# 1A18J1_1A21J1_A.net
KiCad netlist of a schematic drawn in Altium Designer
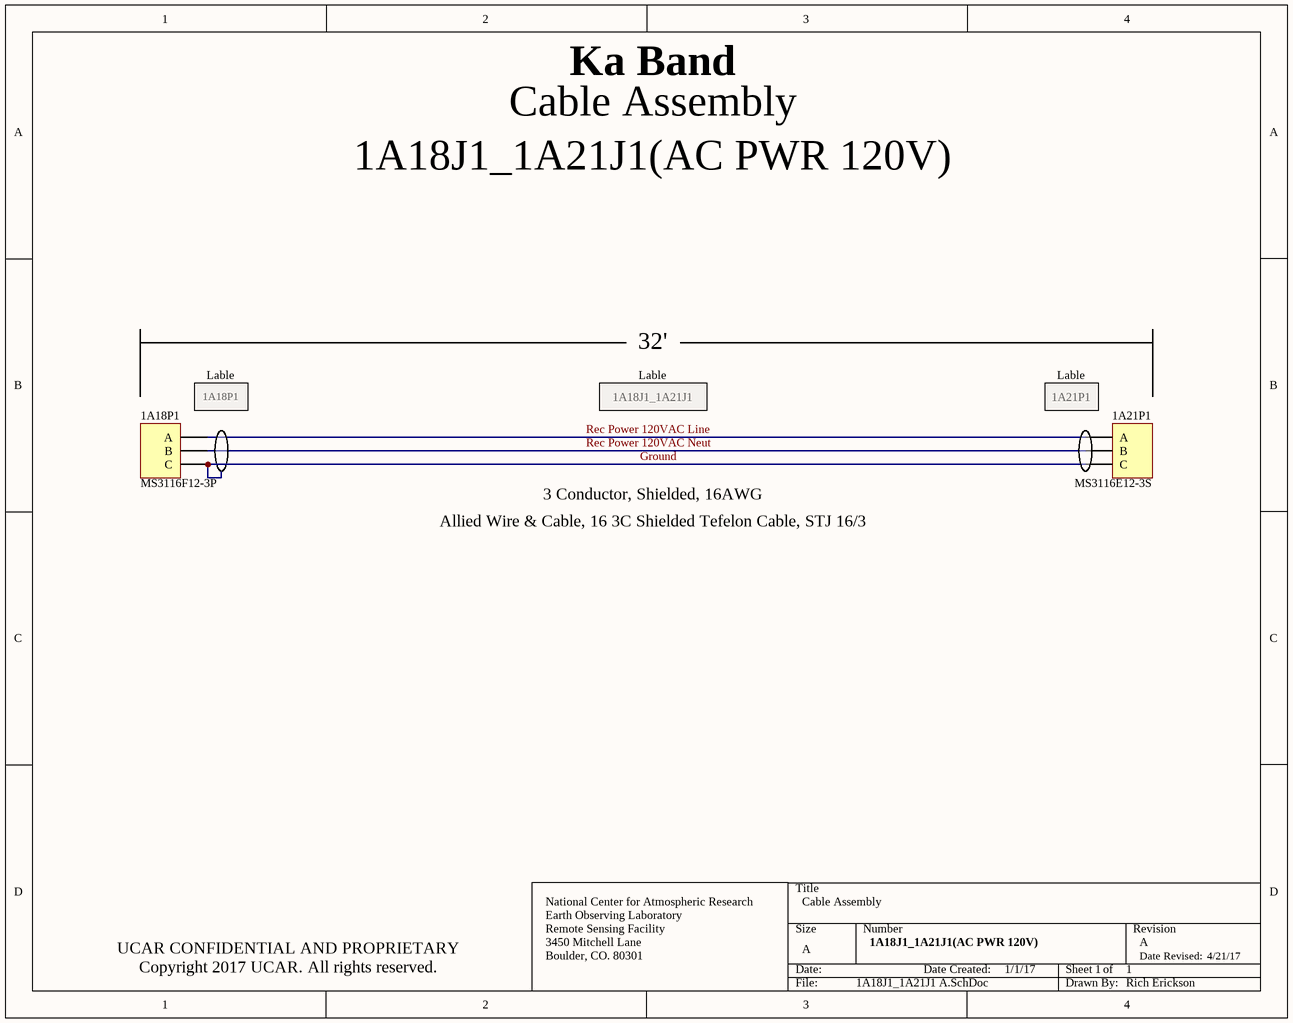
[diagram p0: 1A18J1_1A21J1 A.SchDoc]

(export (version "E")
  (design (tool "Eeschema 10.0.6"))
  (components
    (comp (ref "1A18P1")
      (value "MS3116F12-3P")
      (footprint "HDR1X3")
      (description "Header, 3-Pin")
      (fields (field (name "PUBLISHER") "Altium Limited"))
      (libsource (lib "Miscellaneous Connectors") (part "Header 3"))
    )
    (comp (ref "1A21P1")
      (value "MS3116E12-3S")
      (footprint "HDR1X3")
      (description "Header, 3-Pin")
      (fields (field (name "PUBLISHER") "Altium Limited"))
      (libsource (lib "") (part "Header 3_1"))
    )
  )
  (nets
    (net (code "1") (name "/Ground") (class "Default")
      (node (ref "1A18P1") (pin "3") (pinfunction "C_3") (pintype "passive"))
      (node (ref "1A21P1") (pin "3") (pinfunction "C_3") (pintype "passive"))
    )
    (net (code "2") (name "/Rec Power 120VAC Line") (class "Default")
      (node (ref "1A18P1") (pin "1") (pinfunction "A_1") (pintype "passive"))
      (node (ref "1A21P1") (pin "1") (pinfunction "A_1") (pintype "passive"))
    )
    (net (code "3") (name "/Rec Power 120VAC Neut") (class "Default")
      (node (ref "1A18P1") (pin "2") (pinfunction "B_2") (pintype "passive"))
      (node (ref "1A21P1") (pin "2") (pinfunction "B_2") (pintype "passive"))
    )
  )
)
